# autres_ressouces_sch_ma.net
KiCad netlist of a schematic drawn in Altium Designer
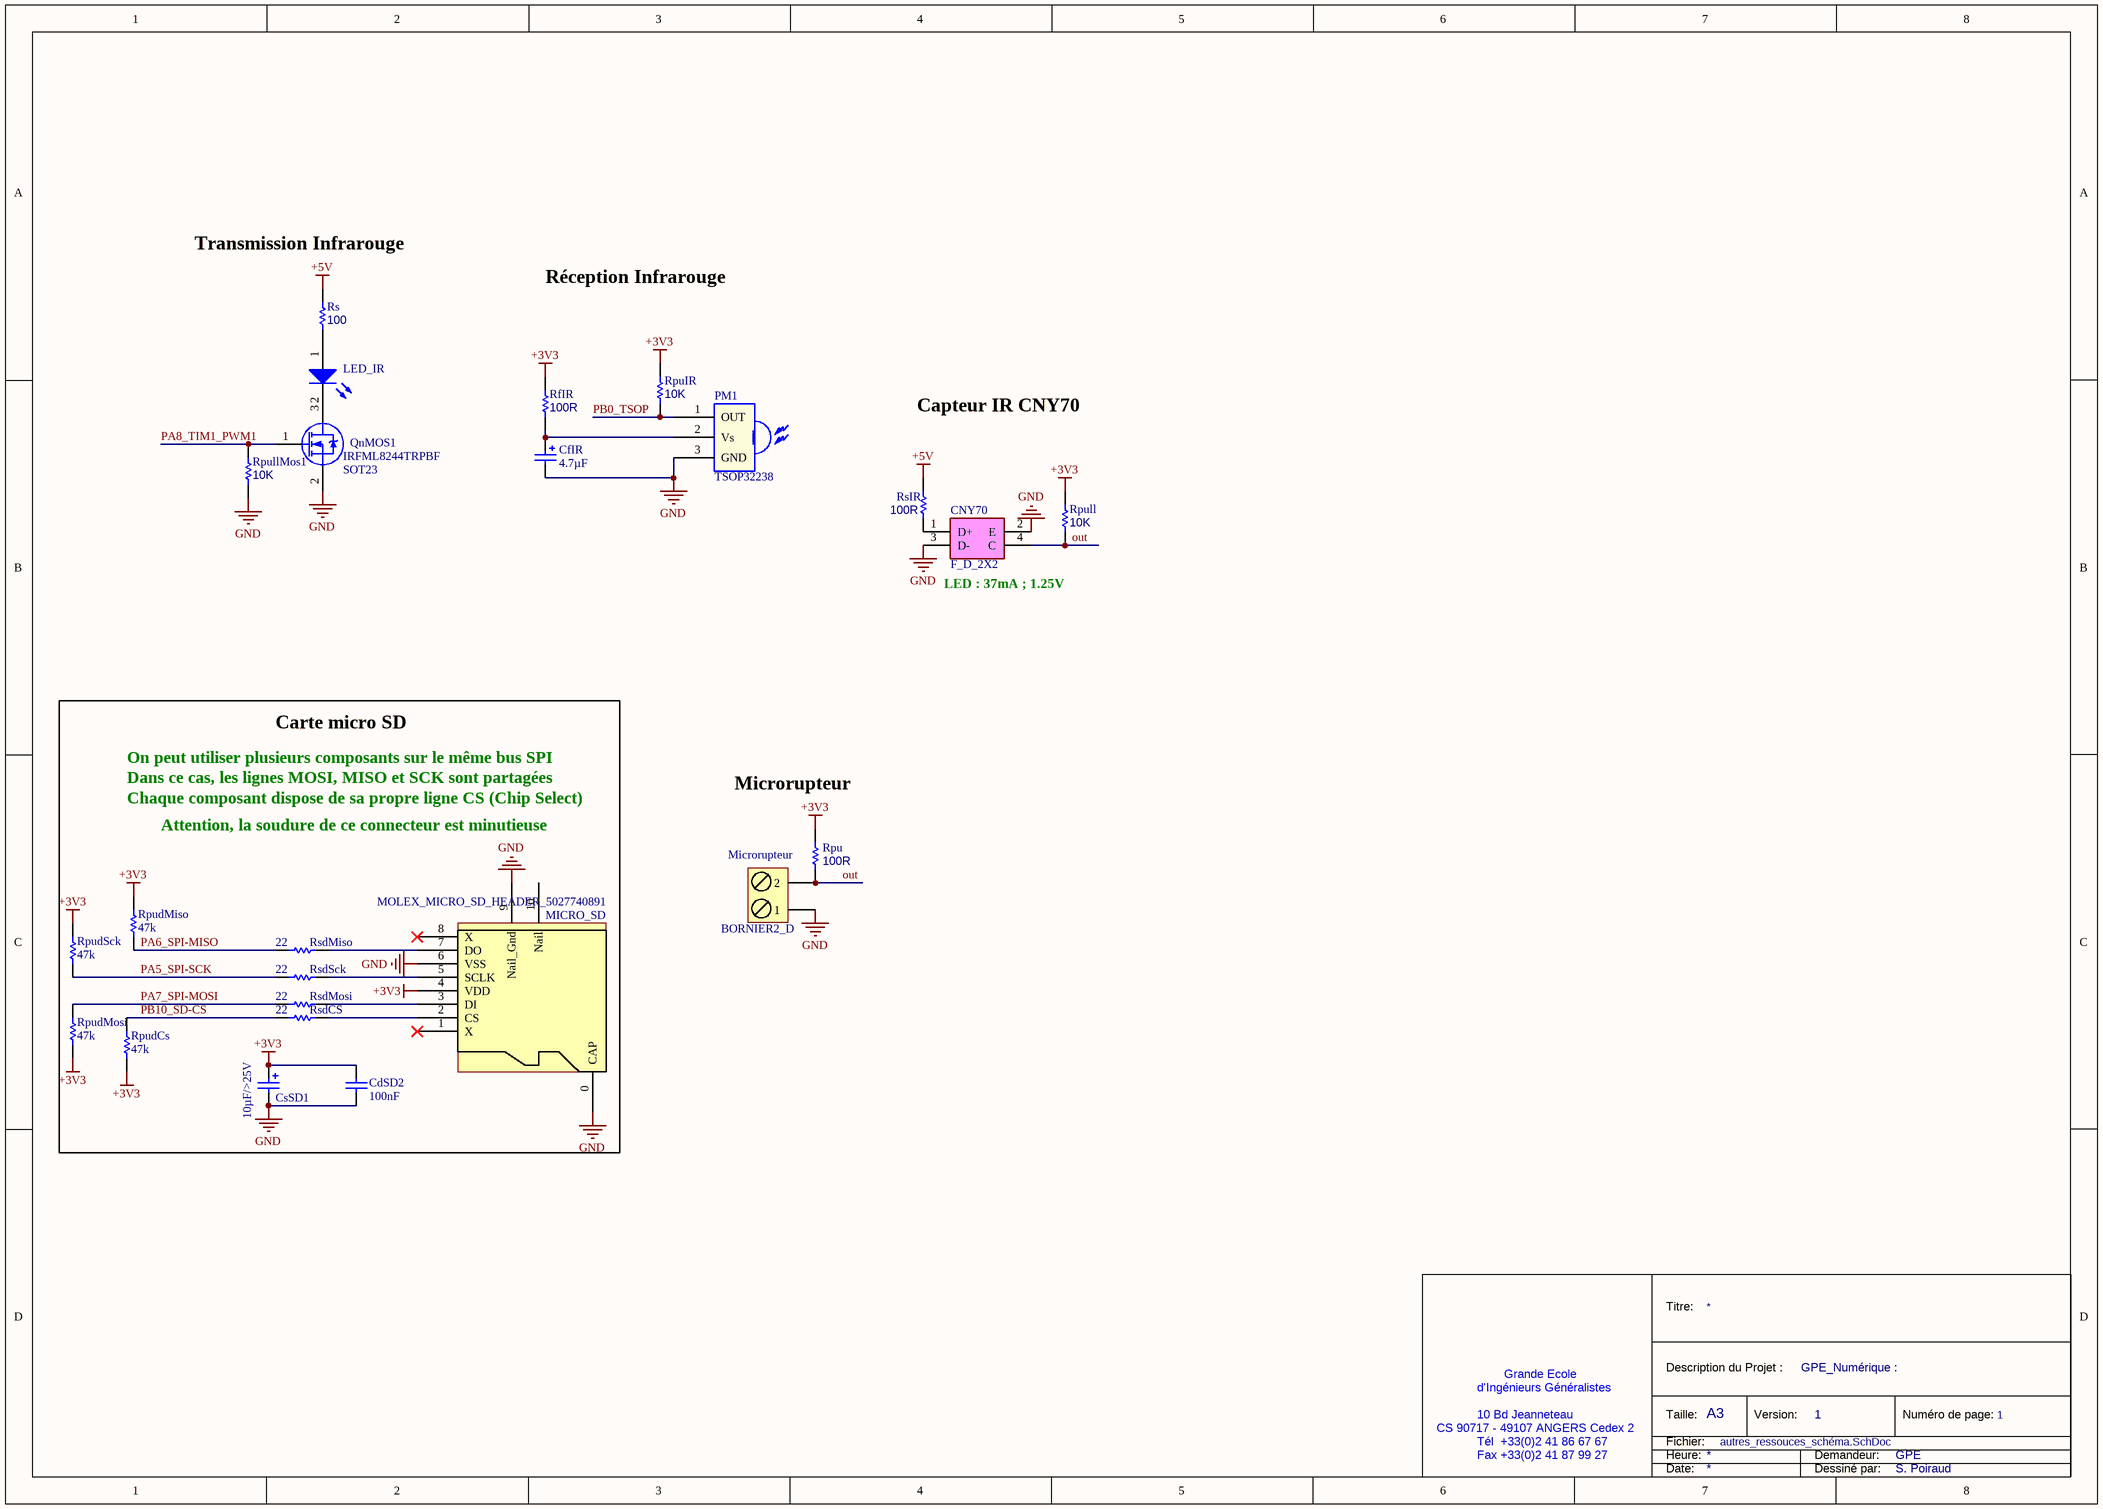
[diagram p0: autres_ressouces_schéma.SchDoc]

(export (version "E")
  (design (tool "Eeschema 10.0.6"))
  (components
    (comp (ref "CdSD2")
      (value "100nF")
      (footprint "CONDENSATEUR_CERAMIQUE_RADIAL_5.08")
      (description "Capacitor")
      (fields (field (name "PUBLISHER") "Altium Limited"))
      (libsource (lib "_ROBOT") (part "Condensateur"))
    )
    (comp (ref "CfIR")
      (value "4.7µF")
      (footprint "CONDENSATEUR_POLARISE_ELECTROLYTIQUE_RADIAL_2.0/5.08")
      (description "CONDENSATEUR POLARISE ELECTROLYTIQUE RADIAL 2.0/5.08")
      (fields (field (name "Comment") "CONDENSATEUR_POL_ELECTROLY_RAD_2.0/5.08"))
      (libsource (lib "composants passifs") (part "CONDENSATEUR_POL_ELECTROLY_RAD_2.0/5.08"))
    )
    (comp (ref "CNY70")
      (value "BARRETTE 2 CONTACTS 2 RANGEES FEMELLE DROITE")
      (footprint "BARRETTE_2X2_F_D")
      (fields (field (name "TYPE") "F_D_2X2"))
      (libsource (lib "connecteurs") (part "BARRETTE_2 CONTACTS_2 RANGEES_FEMELLE_DROITE"))
    )
    (comp (ref "CsSD1")
      (value "10µF/>25V")
      (footprint "CONDENSATEUR_POLARISE_ELECTROLYTIQUE_RADIAL_2.0/5.08")
      (description "CONDENSATEUR POLARISE ELECTROLYTIQUE RADIAL 2.0/5.08")
      (fields (field (name "Comment") "CONDENSATEUR_POL_ELECTROLY_RAD_2.0/5.08"))
      (libsource (lib "composants passifs") (part "CONDENSATEUR_POL_ELECTROLY_RAD_2.0/5.08"))
    )
    (comp (ref "D2")
      (value "LED_3MM")
      (footprint "LED_3MM")
      (description "LED 3MM - ROUGE/VERTE/JAUNE")
      (fields (field (name "TYPE") "LED_IR"))
      (libsource (lib "affichage") (part "LED_3MM"))
    )
    (comp (ref "Microrupteur")
      (value "BORNIER2 DROIT A VIS")
      (footprint "BORNIER2_A_VIS")
      (description "BORNIER 2 PLOTS DROIT A VIS 5.08mm")
      (fields (field (name "TYPE") "BORNIER2_D"))
      (libsource (lib "connecteurs") (part "BORNIER2_DROIT_A VIS"))
    )
    (comp (ref "MICRO_SD")
      (value "MOLEX_MICRO_SD_HEADER_5027740891")
      (footprint "MOLEX_MICRO_SD_HEADER_5027740891")
      (libsource (lib "Connecteur") (part "MOLEX_MICRO_SD_HEADER_5027740891"))
    )
    (comp (ref "PM1")
      (value "RECEPTEUR_INFRAROUGE_TSOP32238")
      (footprint "RECEPTEUR_INFRAROUGE_TSOP32238")
      (description "RECEPTEUR_INFRAROUGE_TSOP32238_38kHz")
      (fields (field (name "TYPE") "TSOP32238"))
      (libsource (lib "affichage") (part "RECEPTEUR_INFRAROUGE_TSOP32238_38kHz"))
    )
    (comp (ref "QnMOS1")
      (value "TRANSISTOR_MOSFET-N_SOT23_GSD")
      (footprint "TRANSISTOR_MOSFET-N_SOT23_GSD")
      (description "TRANSISTOR MOSFET CANAL N BOITIER SOT23_GSD")
      (fields (field (name "TYPE") "IRFML8244TRPBF") (field (name "PACKAGE") "SOT23"))
      (libsource (lib "composants actifs") (part "TRANSISTOR_MOSFET-N_SOT23_GSD"))
    )
    (comp (ref "RfIR")
      (value "100R")
      (footprint "RESISTANCE_1/4W")
      (description "RESISTANCE TRAVERSANTE AXIALE 1/4W")
      (fields (field (name "Comment") "RESISTANCE_AXIALE_1/4W"))
      (libsource (lib "composants passifs") (part "RESISTANCE_AXIALE_1/4W"))
    )
    (comp (ref "Rpu")
      (value "100R")
      (footprint "RESISTANCE_1/4W")
      (description "RESISTANCE TRAVERSANTE AXIALE 1/4W")
      (fields (field (name "Comment") "RESISTANCE_AXIALE_1/4W"))
      (libsource (lib "composants passifs") (part "RESISTANCE_AXIALE_1/4W"))
    )
    (comp (ref "RpudCs")
      (value "47k")
      (footprint "RESISTANCE_1/4W")
      (description "Resistor")
      (fields (field (name "PUBLISHER") "Altium Limited"))
      (libsource (lib "_ROBOT") (part "Resistor"))
    )
    (comp (ref "RpudMiso")
      (value "47k")
      (footprint "RESISTANCE_1/4W")
      (description "Resistor")
      (fields (field (name "PUBLISHER") "Altium Limited"))
      (libsource (lib "_ROBOT") (part "Resistor"))
    )
    (comp (ref "RpudMosi")
      (value "47k")
      (footprint "RESISTANCE_1/4W")
      (description "Resistor")
      (fields (field (name "PUBLISHER") "Altium Limited"))
      (libsource (lib "_ROBOT") (part "Resistor"))
    )
    (comp (ref "RpudSck")
      (value "47k")
      (footprint "RESISTANCE_1/4W")
      (description "Resistor")
      (fields (field (name "PUBLISHER") "Altium Limited"))
      (libsource (lib "_ROBOT") (part "Resistor"))
    )
    (comp (ref "RpuIR")
      (value "10K")
      (footprint "RESISTANCE_1/4W")
      (description "RESISTANCE TRAVERSANTE AXIALE 1/4W")
      (fields (field (name "Comment") "RESISTANCE_AXIALE_1/4W"))
      (libsource (lib "composants passifs") (part "RESISTANCE_AXIALE_1/4W"))
    )
    (comp (ref "Rpull")
      (value "10K")
      (footprint "RESISTANCE_1/4W")
      (description "RESISTANCE TRAVERSANTE AXIALE 1/4W")
      (fields (field (name "Comment") "RESISTANCE_AXIALE_1/4W"))
      (libsource (lib "composants passifs") (part "RESISTANCE_AXIALE_1/4W"))
    )
    (comp (ref "RpullMos1")
      (value "10K")
      (footprint "RESISTANCE_1/4W")
      (description "RESISTANCE TRAVERSANTE AXIALE 1/4W")
      (fields (field (name "Comment") "RESISTANCE_AXIALE_1/4W"))
      (libsource (lib "composants passifs") (part "RESISTANCE_AXIALE_1/4W"))
    )
    (comp (ref "Rs")
      (value "100")
      (footprint "RESISTANCE_1/4W")
      (description "RESISTANCE TRAVERSANTE AXIALE 1/4W")
      (fields (field (name "Comment") "RESISTANCE_AXIALE_1/4W"))
      (libsource (lib "composants passifs") (part "RESISTANCE_AXIALE_1/4W"))
    )
    (comp (ref "RsdCS")
      (value "22")
      (footprint "RESISTANCE_1/4W")
      (description "Resistor")
      (fields (field (name "PUBLISHER") "Altium Limited"))
      (libsource (lib "_ROBOT") (part "Resistor"))
    )
    (comp (ref "RsdMiso")
      (value "22")
      (footprint "RESISTANCE_1/4W")
      (description "Resistor")
      (fields (field (name "PUBLISHER") "Altium Limited"))
      (libsource (lib "_ROBOT") (part "Resistor"))
    )
    (comp (ref "RsdMosi")
      (value "22")
      (footprint "RESISTANCE_1/4W")
      (description "Resistor")
      (fields (field (name "PUBLISHER") "Altium Limited"))
      (libsource (lib "_ROBOT") (part "Resistor"))
    )
    (comp (ref "RsdSck")
      (value "22")
      (footprint "RESISTANCE_1/4W")
      (description "Resistor")
      (fields (field (name "PUBLISHER") "Altium Limited"))
      (libsource (lib "_ROBOT") (part "Resistor"))
    )
    (comp (ref "RsIR")
      (value "100R")
      (footprint "RESISTANCE_1/4W")
      (description "RESISTANCE TRAVERSANTE AXIALE 1/4W")
      (fields (field (name "Comment") "RESISTANCE_AXIALE_1/4W"))
      (libsource (lib "composants passifs") (part "RESISTANCE_AXIALE_1/4W"))
    )
  )
  (nets
    (net (code "1") (name "+3V3") (class "Default")
      (node (ref "CdSD2") (pin "2") (pinfunction "2_2") (pintype "passive"))
      (node (ref "CsSD1") (pin "1") (pinfunction "1_1") (pintype "passive"))
      (node (ref "MICRO_SD") (pin "4") (pinfunction "VDD_4") (pintype "passive"))
      (node (ref "RfIR") (pin "1") (pinfunction "1_1") (pintype "passive"))
      (node (ref "Rpu") (pin "1") (pinfunction "1_1") (pintype "passive"))
      (node (ref "RpuIR") (pin "1") (pinfunction "1_1") (pintype "passive"))
      (node (ref "RpudCs") (pin "1") (pinfunction "1_1") (pintype "passive"))
      (node (ref "RpudMiso") (pin "2") (pinfunction "2_2") (pintype "passive"))
      (node (ref "RpudMosi") (pin "1") (pinfunction "1_1") (pintype "passive"))
      (node (ref "RpudSck") (pin "2") (pinfunction "2_2") (pintype "passive"))
      (node (ref "Rpull") (pin "1") (pinfunction "1_1") (pintype "passive"))
    )
    (net (code "2") (name "+5V") (class "Default")
      (node (ref "Rs") (pin "2") (pinfunction "2_2") (pintype "passive"))
      (node (ref "RsIR") (pin "1") (pinfunction "1_1") (pintype "passive"))
    )
    (net (code "3") (name "/PA5_SPI-SCK") (class "Default")
      (node (ref "RpudSck") (pin "1") (pinfunction "1_1") (pintype "passive"))
      (node (ref "RsdSck") (pin "1") (pinfunction "1_1") (pintype "passive"))
    )
    (net (code "4") (name "/PA6_SPI-MISO") (class "Default")
      (node (ref "RpudMiso") (pin "1") (pinfunction "1_1") (pintype "passive"))
      (node (ref "RsdMiso") (pin "1") (pinfunction "1_1") (pintype "passive"))
    )
    (net (code "5") (name "/PA7_SPI-MOSI") (class "Default")
      (node (ref "RpudMosi") (pin "2") (pinfunction "2_2") (pintype "passive"))
      (node (ref "RsdMosi") (pin "1") (pinfunction "1_1") (pintype "passive"))
    )
    (net (code "6") (name "/PA8_TIM1_PWM1") (class "Default")
      (node (ref "QnMOS1") (pin "1") (pinfunction "G_1") (pintype "passive"))
      (node (ref "RpullMos1") (pin "2") (pinfunction "2_2") (pintype "passive"))
    )
    (net (code "7") (name "/PB0_TSOP") (class "Default")
      (node (ref "PM1") (pin "1") (pinfunction "OUT_1") (pintype "passive"))
      (node (ref "RpuIR") (pin "2") (pinfunction "2_2") (pintype "passive"))
    )
    (net (code "8") (name "/PB10_SD-CS") (class "Default")
      (node (ref "RpudCs") (pin "2") (pinfunction "2_2") (pintype "passive"))
      (node (ref "RsdCS") (pin "1") (pinfunction "1_1") (pintype "passive"))
    )
    (net (code "9") (name "/out") (class "Default")
      (node (ref "CNY70") (pin "4") (pinfunction "C_4") (pintype "passive"))
      (node (ref "Microrupteur") (pin "2") (pinfunction "2_2") (pintype "passive"))
      (node (ref "Rpu") (pin "2") (pinfunction "2_2") (pintype "passive"))
      (node (ref "Rpull") (pin "2") (pinfunction "2_2") (pintype "passive"))
    )
    (net (code "10") (name "GND") (class "Default")
      (node (ref "CNY70") (pin "2") (pinfunction "E_2") (pintype "passive"))
      (node (ref "CNY70") (pin "3") (pinfunction "D-_3") (pintype "passive"))
      (node (ref "CdSD2") (pin "1") (pinfunction "1_1") (pintype "passive"))
      (node (ref "CfIR") (pin "2") (pinfunction "2_2") (pintype "passive"))
      (node (ref "CsSD1") (pin "2") (pinfunction "2_2") (pintype "passive"))
      (node (ref "MICRO_SD") (pin "0") (pinfunction "CAP_0") (pintype "passive"))
      (node (ref "MICRO_SD") (pin "6") (pinfunction "VSS_6") (pintype "passive"))
      (node (ref "MICRO_SD") (pin "9") (pinfunction "Nail_Gnd_9") (pintype "passive"))
      (node (ref "Microrupteur") (pin "1") (pinfunction "1_1") (pintype "passive"))
      (node (ref "PM1") (pin "3") (pinfunction "GND_3") (pintype "passive"))
      (node (ref "QnMOS1") (pin "2") (pinfunction "S_2") (pintype "passive"))
      (node (ref "RpullMos1") (pin "1") (pinfunction "1_1") (pintype "passive"))
    )
    (net (code "11") (name "Net-(CNY70-D+)") (class "Default")
      (node (ref "CNY70") (pin "1") (pinfunction "D+_1") (pintype "passive"))
      (node (ref "RsIR") (pin "2") (pinfunction "2_2") (pintype "passive"))
    )
    (net (code "12") (name "Net-(D2-Pad1)") (class "Default")
      (node (ref "D2") (pin "1") (pinfunction "1_1") (pintype "passive"))
      (node (ref "Rs") (pin "1") (pinfunction "1_1") (pintype "passive"))
    )
    (net (code "13") (name "Net-(MICRO_SD-CS)") (class "Default")
      (node (ref "MICRO_SD") (pin "2") (pinfunction "CS_2") (pintype "passive"))
      (node (ref "RsdCS") (pin "2") (pinfunction "2_2") (pintype "passive"))
    )
    (net (code "14") (name "Net-(MICRO_SD-DI)") (class "Default")
      (node (ref "MICRO_SD") (pin "3") (pinfunction "DI_3") (pintype "passive"))
      (node (ref "RsdMosi") (pin "2") (pinfunction "2_2") (pintype "passive"))
    )
    (net (code "15") (name "Net-(MICRO_SD-DO)") (class "Default")
      (node (ref "MICRO_SD") (pin "7") (pinfunction "DO_7") (pintype "passive"))
      (node (ref "RsdMiso") (pin "2") (pinfunction "2_2") (pintype "passive"))
    )
    (net (code "16") (name "Net-(MICRO_SD-SCLK)") (class "Default")
      (node (ref "MICRO_SD") (pin "5") (pinfunction "SCLK_5") (pintype "passive"))
      (node (ref "RsdSck") (pin "2") (pinfunction "2_2") (pintype "passive"))
    )
    (net (code "17") (name "Net-(PM1-Vs)") (class "Default")
      (node (ref "CfIR") (pin "1") (pinfunction "1_1") (pintype "passive"))
      (node (ref "PM1") (pin "2") (pinfunction "Vs_2") (pintype "passive"))
      (node (ref "RfIR") (pin "2") (pinfunction "2_2") (pintype "passive"))
    )
    (net (code "18") (name "unconnected-(D2-Pad2)") (class "Default")
      (node (ref "D2") (pin "2") (pinfunction "2_2") (pintype "passive"))
    )
    (net (code "19") (name "unconnected-(MICRO_SD-Nail-Pad10)") (class "Default")
      (node (ref "MICRO_SD") (pin "10") (pinfunction "Nail_10") (pintype "passive"))
    )
    (net (code "20") (name "unconnected-(MICRO_SD-X-Pad1)") (class "Default")
      (node (ref "MICRO_SD") (pin "1") (pinfunction "X_1") (pintype "passive+no_connect"))
    )
    (net (code "21") (name "unconnected-(MICRO_SD-X-Pad8)") (class "Default")
      (node (ref "MICRO_SD") (pin "8") (pinfunction "X_8") (pintype "passive+no_connect"))
    )
    (net (code "22") (name "unconnected-(QnMOS1-D-Pad3)") (class "Default")
      (node (ref "QnMOS1") (pin "3") (pinfunction "D_3") (pintype "passive"))
    )
  )
)
